# Dual_Hbridge.net
KiCad netlist of a schematic drawn in EAGLE
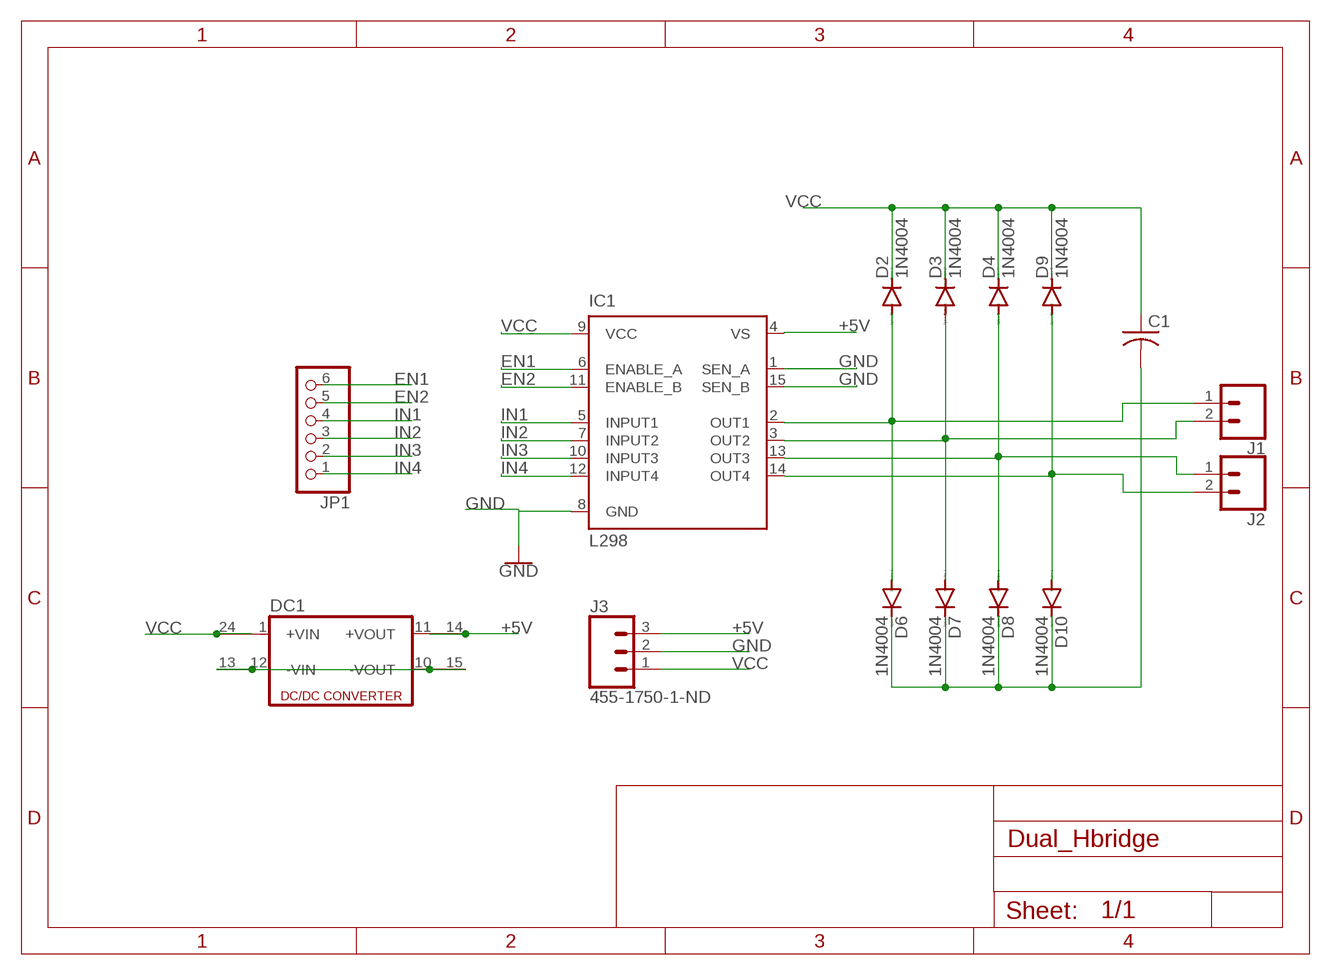
[diagram p0: schematic, sheet 1]

(export (version "E")
  (design (tool "Eeschema 10.0.6"))
  (components
    (comp (ref "C1")
      (value "C-US025-024X044")
      (footprint "eagle-import:C025-024X044")
      (libsource (lib "eagle-import") (part "C-US025-024X044"))
    )
    (comp (ref "D2")
      (value "1N4004")
      (footprint "eagle-import:DO41-10")
      (libsource (lib "eagle-import") (part "1N4004"))
    )
    (comp (ref "D3")
      (value "1N4004")
      (footprint "eagle-import:DO41-10")
      (libsource (lib "eagle-import") (part "1N4004"))
    )
    (comp (ref "D4")
      (value "1N4004")
      (footprint "eagle-import:DO41-10")
      (libsource (lib "eagle-import") (part "1N4004"))
    )
    (comp (ref "D6")
      (value "1N4004")
      (footprint "eagle-import:DO41-10")
      (libsource (lib "eagle-import") (part "1N4004"))
    )
    (comp (ref "D7")
      (value "1N4004")
      (footprint "eagle-import:DO41-10")
      (libsource (lib "eagle-import") (part "1N4004"))
    )
    (comp (ref "D8")
      (value "1N4004")
      (footprint "eagle-import:DO41-10")
      (libsource (lib "eagle-import") (part "1N4004"))
    )
    (comp (ref "D9")
      (value "1N4004")
      (footprint "eagle-import:DO41-10")
      (libsource (lib "eagle-import") (part "1N4004"))
    )
    (comp (ref "D10")
      (value "1N4004")
      (footprint "eagle-import:DO41-10")
      (libsource (lib "eagle-import") (part "1N4004"))
    )
    (comp (ref "DC1")
      (value "DC213R")
      (footprint "eagle-import:CMK")
      (libsource (lib "eagle-import") (part "DC213R"))
    )
    (comp (ref "IC1")
      (value "L298")
      (footprint "eagle-import:MULTIWATT-15")
      (fields (field (name "MPN") "L298N"))
      (libsource (lib "eagle-import") (part "L298"))
    )
    (comp (ref "J1")
      (value "CONN_02")
      (footprint "eagle-import:1X02")
      (libsource (lib "eagle-import") (part "CONN_02"))
    )
    (comp (ref "J2")
      (value "CONN_02")
      (footprint "eagle-import:1X02")
      (libsource (lib "eagle-import") (part "CONN_02"))
    )
    (comp (ref "J3")
      (value "455-1750-1-ND")
      (footprint "eagle-import:1X03")
      (libsource (lib "eagle-import") (part "CONN_03"))
    )
    (comp (ref "JP1")
      (value "PINHD-1X6")
      (footprint "eagle-import:1X06")
      (libsource (lib "eagle-import") (part "PINHD-1X6"))
    )
  )
  (nets
    (net (code "1") (name "/+5V") (class "Default")
      (node (ref "DC1") (pin "11") (pinfunction "+VOUT_11") (pintype "passive"))
      (node (ref "DC1") (pin "14") (pinfunction "+VOUT1_14") (pintype "passive"))
      (node (ref "IC1") (pin "4") (pinfunction "VS_4") (pintype "power_in"))
      (node (ref "J3") (pin "3") (pinfunction "3_3") (pintype "passive"))
    )
    (net (code "2") (name "/EN1") (class "Default")
      (node (ref "IC1") (pin "6") (pinfunction "ENABLE_A_6") (pintype "input"))
      (node (ref "JP1") (pin "6") (pinfunction "6_6") (pintype "passive"))
    )
    (net (code "3") (name "/EN2") (class "Default")
      (node (ref "IC1") (pin "11") (pinfunction "ENABLE_B_11") (pintype "input"))
      (node (ref "JP1") (pin "5") (pinfunction "5_5") (pintype "passive"))
    )
    (net (code "4") (name "/IN1") (class "Default")
      (node (ref "IC1") (pin "5") (pinfunction "INPUT1_5") (pintype "input"))
      (node (ref "JP1") (pin "4") (pinfunction "4_4") (pintype "passive"))
    )
    (net (code "5") (name "/IN2") (class "Default")
      (node (ref "IC1") (pin "7") (pinfunction "INPUT2_7") (pintype "input"))
      (node (ref "JP1") (pin "3") (pinfunction "3_3") (pintype "passive"))
    )
    (net (code "6") (name "/IN3") (class "Default")
      (node (ref "IC1") (pin "10") (pinfunction "INPUT3_10") (pintype "input"))
      (node (ref "JP1") (pin "2") (pinfunction "2_2") (pintype "passive"))
    )
    (net (code "7") (name "/IN4") (class "Default")
      (node (ref "IC1") (pin "12") (pinfunction "INPUT4_12") (pintype "input"))
      (node (ref "JP1") (pin "1") (pinfunction "1_1") (pintype "passive"))
    )
    (net (code "8") (name "/VCC") (class "Default")
      (node (ref "C1") (pin "1") (pinfunction "1_1") (pintype "passive"))
      (node (ref "D2") (pin "C") (pinfunction "C_C") (pintype "passive"))
      (node (ref "D3") (pin "C") (pinfunction "C_C") (pintype "passive"))
      (node (ref "D4") (pin "C") (pinfunction "C_C") (pintype "passive"))
      (node (ref "D9") (pin "C") (pinfunction "C_C") (pintype "passive"))
      (node (ref "DC1") (pin "1") (pinfunction "+VIN_1") (pintype "passive"))
      (node (ref "DC1") (pin "24") (pinfunction "+VIN1_24") (pintype "passive"))
      (node (ref "IC1") (pin "9") (pinfunction "VCC_9") (pintype "power_in"))
      (node (ref "J3") (pin "1") (pinfunction "1_1") (pintype "passive"))
    )
    (net (code "9") (name "GND") (class "Default")
      (node (ref "IC1") (pin "1") (pinfunction "SEN_A_1") (pintype "input"))
      (node (ref "IC1") (pin "15") (pinfunction "SEN_B_15") (pintype "input"))
      (node (ref "IC1") (pin "8") (pinfunction "GND_8") (pintype "power_in"))
      (node (ref "J3") (pin "2") (pinfunction "2_2") (pintype "passive"))
    )
    (net (code "10") (name "Net-(C1-Pad2)") (class "Default")
      (node (ref "C1") (pin "2") (pinfunction "2_2") (pintype "passive"))
      (node (ref "D10") (pin "C") (pinfunction "C_C") (pintype "passive"))
      (node (ref "D6") (pin "C") (pinfunction "C_C") (pintype "passive"))
      (node (ref "D7") (pin "C") (pinfunction "C_C") (pintype "passive"))
      (node (ref "D8") (pin "C") (pinfunction "C_C") (pintype "passive"))
    )
    (net (code "11") (name "Net-(DC1--VIN)") (class "Default")
      (node (ref "DC1") (pin "10") (pinfunction "-VOUT_10") (pintype "passive"))
      (node (ref "DC1") (pin "12") (pinfunction "-VIN_12") (pintype "passive"))
      (node (ref "DC1") (pin "13") (pinfunction "-VIN1_13") (pintype "passive"))
      (node (ref "DC1") (pin "15") (pinfunction "-VOUT1_15") (pintype "passive"))
    )
    (net (code "12") (name "Net-(IC1-OUT1)") (class "Default")
      (node (ref "D2") (pin "A") (pinfunction "A_A") (pintype "passive"))
      (node (ref "D6") (pin "A") (pinfunction "A_A") (pintype "passive"))
      (node (ref "IC1") (pin "2") (pinfunction "OUT1_2") (pintype "output"))
      (node (ref "J1") (pin "1") (pinfunction "1_1") (pintype "passive"))
    )
    (net (code "13") (name "Net-(IC1-OUT2)") (class "Default")
      (node (ref "D3") (pin "A") (pinfunction "A_A") (pintype "passive"))
      (node (ref "D7") (pin "A") (pinfunction "A_A") (pintype "passive"))
      (node (ref "IC1") (pin "3") (pinfunction "OUT2_3") (pintype "output"))
      (node (ref "J1") (pin "2") (pinfunction "2_2") (pintype "passive"))
    )
    (net (code "14") (name "Net-(IC1-OUT3)") (class "Default")
      (node (ref "D4") (pin "A") (pinfunction "A_A") (pintype "passive"))
      (node (ref "D8") (pin "A") (pinfunction "A_A") (pintype "passive"))
      (node (ref "IC1") (pin "13") (pinfunction "OUT3_13") (pintype "output"))
      (node (ref "J2") (pin "1") (pinfunction "1_1") (pintype "passive"))
    )
    (net (code "15") (name "Net-(IC1-OUT4)") (class "Default")
      (node (ref "D10") (pin "A") (pinfunction "A_A") (pintype "passive"))
      (node (ref "D9") (pin "A") (pinfunction "A_A") (pintype "passive"))
      (node (ref "IC1") (pin "14") (pinfunction "OUT4_14") (pintype "output"))
      (node (ref "J2") (pin "2") (pinfunction "2_2") (pintype "passive"))
    )
  )
)
